# 1_dif_comp_stage.net
KiCad netlist of a schematic drawn in Altium Designer
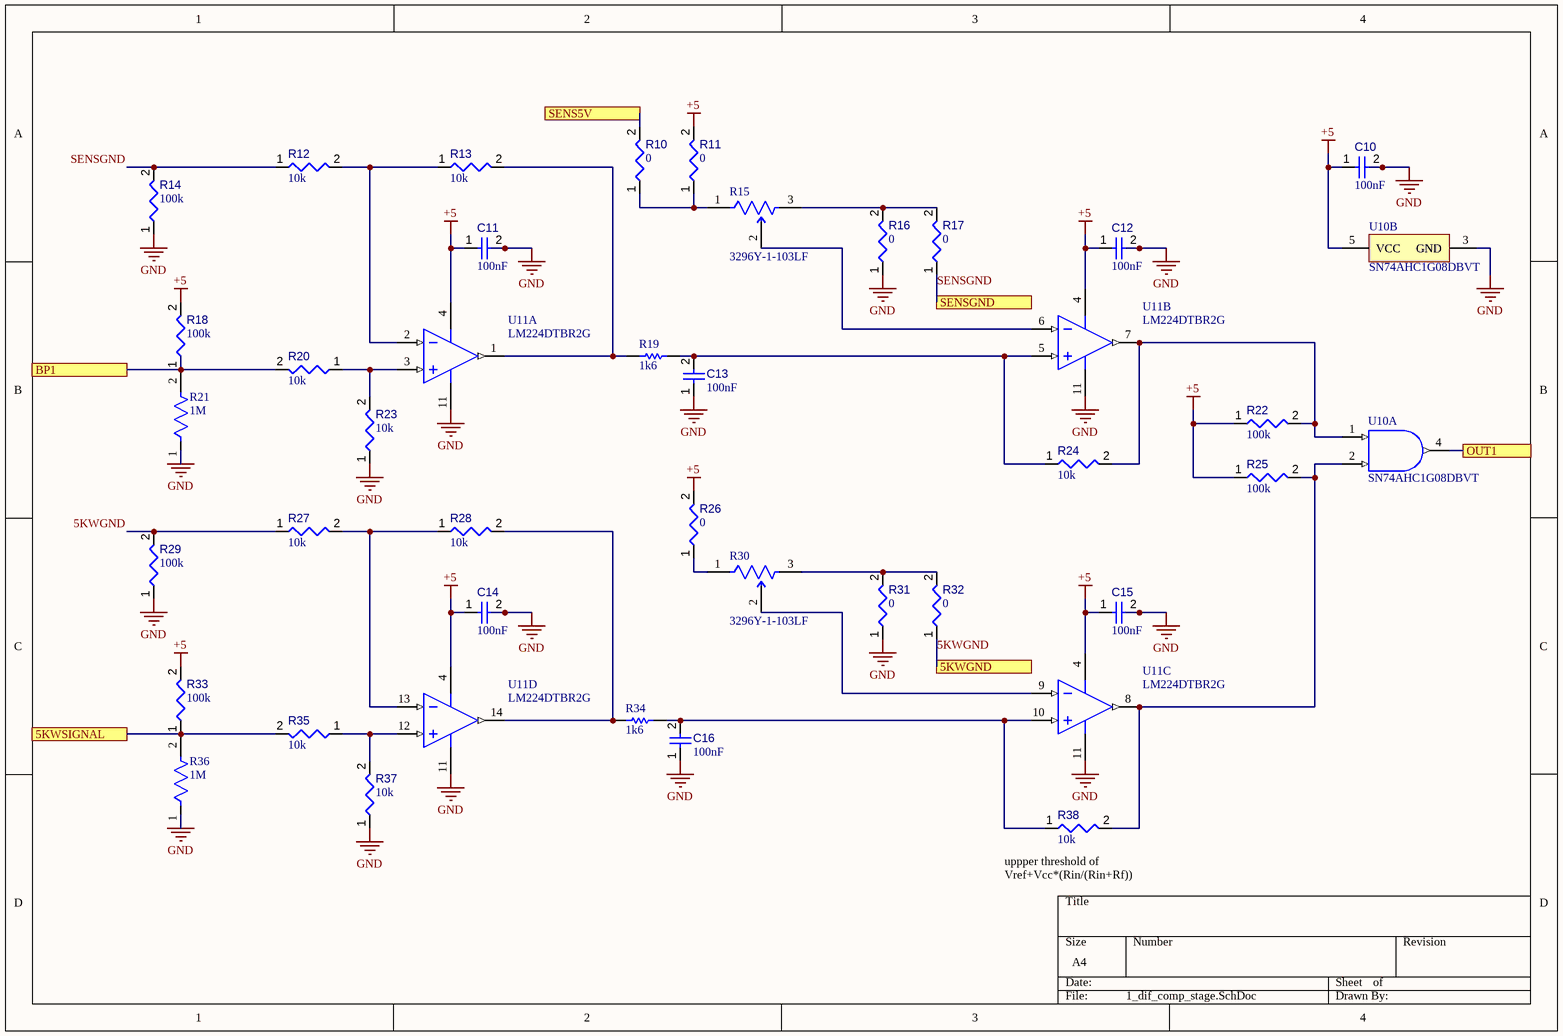
[diagram p0: 1_dif_comp_stage.SchDoc]

(export (version "E")
  (design (tool "Eeschema 10.0.6"))
  (components
    (comp (ref "C10")
      (value "100nF")
      (footprint "CAPC1608X90X40NL10T20")
      (description "Chip Capacitor, 100 nF, +/- 10%, 50 V, 0603 (1608 Metric)")
      (fields (field (name "TOLERANCE") "10%") (field (name "Comment") "Capacitor 100 nF +/-10% 50 V 0603"))
      (libsource (lib "UNSW Redback Racing") (part "CAP-NP-2"))
    )
    (comp (ref "C11")
      (value "100nF")
      (footprint "CAPC1608X90X40NL10T20")
      (description "Chip Capacitor, 100 nF, +/- 10%, 50 V, 0603 (1608 Metric)")
      (fields (field (name "TOLERANCE") "10%") (field (name "Comment") "Capacitor 100 nF +/-10% 50 V 0603"))
      (libsource (lib "UNSW Redback Racing") (part "CAP-NP-2"))
    )
    (comp (ref "C12")
      (value "100nF")
      (footprint "CAPC1608X90X40NL10T20")
      (description "Chip Capacitor, 100 nF, +/- 10%, 50 V, 0603 (1608 Metric)")
      (fields (field (name "TOLERANCE") "10%") (field (name "Comment") "Capacitor 100 nF +/-10% 50 V 0603"))
      (libsource (lib "UNSW Redback Racing") (part "CAP-NP-2"))
    )
    (comp (ref "C13")
      (value "100nF")
      (footprint "CAPC1608X90X40NL10T20")
      (description "Chip Capacitor, 100 nF, +/- 10%, 50 V, 0603 (1608 Metric)")
      (fields (field (name "TOLERANCE") "10%") (field (name "Comment") "Capacitor 100 nF +/-10% 50 V 0603"))
      (libsource (lib "UNSW Redback Racing") (part "CAP-NP-2"))
    )
    (comp (ref "C14")
      (value "100nF")
      (footprint "CAPC1608X90X40NL10T20")
      (description "Chip Capacitor, 100 nF, +/- 10%, 50 V, 0603 (1608 Metric)")
      (fields (field (name "TOLERANCE") "10%") (field (name "Comment") "Capacitor 100 nF +/-10% 50 V 0603"))
      (libsource (lib "UNSW Redback Racing") (part "CAP-NP-2"))
    )
    (comp (ref "C15")
      (value "100nF")
      (footprint "CAPC1608X90X40NL10T20")
      (description "Chip Capacitor, 100 nF, +/- 10%, 50 V, 0603 (1608 Metric)")
      (fields (field (name "TOLERANCE") "10%") (field (name "Comment") "Capacitor 100 nF +/-10% 50 V 0603"))
      (libsource (lib "UNSW Redback Racing") (part "CAP-NP-2"))
    )
    (comp (ref "C16")
      (value "100nF")
      (footprint "CAPC1608X90X40NL10T20")
      (description "Chip Capacitor, 100 nF, +/- 10%, 50 V, 0603 (1608 Metric)")
      (fields (field (name "TOLERANCE") "10%") (field (name "Comment") "Capacitor 100 nF +/-10% 50 V 0603"))
      (libsource (lib "UNSW Redback Racing") (part "CAP-NP-2"))
    )
    (comp (ref "R10")
      (value "0")
      (footprint "RESC0603(1608)_L")
      (description "Jumper 0603 (1608 Metric)")
      (fields (field (name "Comment") "0R3J"))
      (libsource (lib "UNSW Redback Racing") (part "0R3J"))
    )
    (comp (ref "R11")
      (value "0")
      (footprint "RESC0603(1608)_L")
      (description "Jumper 0603 (1608 Metric)")
      (fields (field (name "Comment") "0R3J"))
      (libsource (lib "UNSW Redback Racing") (part "0R3J"))
    )
    (comp (ref "R12")
      (value "10k")
      (footprint "RESC1608X55X25ML10T15")
      (description "Chip Resistor, 10 KOhm, +/- 1%, 01 W, -55 to 155 degC, 0603 (1608 Metric)")
      (fields (field (name "POWER") "100mW") (field (name "TOLERANCE") "1%"))
      (libsource (lib "UNSW Redback Racing") (part "RES-2"))
    )
    (comp (ref "R13")
      (value "10k")
      (footprint "RESC1608X55X25ML10T15")
      (description "Chip Resistor, 10 KOhm, +/- 1%, 01 W, -55 to 155 degC, 0603 (1608 Metric)")
      (fields (field (name "POWER") "100mW") (field (name "TOLERANCE") "1%"))
      (libsource (lib "UNSW Redback Racing") (part "RES-2"))
    )
    (comp (ref "R14")
      (value "100k")
      (footprint "RESC1608X55X25ML10T15")
      (description "Chip Resistor, 100 KOhm, +/- 1%, 0.1 W, -55 to 155 degC, 0603 (1608 Metric)")
      (fields (field (name "TOLERANCE") "1%") (field (name "POWER") "100mW"))
      (libsource (lib "UNSW Redback Racing") (part "RES-2"))
    )
    (comp (ref "R15")
      (value "3296Y-1-103LF")
      (footprint "FP-3296Y-MFG")
      (description "TRIMMER 10K OHM 0.5W PC PIN TOP")
      (fields (field (name "TOLERANCE") "10%"))
      (libsource (lib "Altium Content Vault") (part "2dcfd2547301a7d3209a5e99acfd772"))
    )
    (comp (ref "R16")
      (value "0")
      (footprint "RESC0603(1608)_L")
      (description "Jumper 0603 (1608 Metric)")
      (fields (field (name "Comment") "0R3J"))
      (libsource (lib "UNSW Redback Racing") (part "0R3J"))
    )
    (comp (ref "R17")
      (value "0")
      (footprint "RESC0603(1608)_L")
      (description "Jumper 0603 (1608 Metric)")
      (fields (field (name "Comment") "0R3J"))
      (libsource (lib "UNSW Redback Racing") (part "0R3J"))
    )
    (comp (ref "R18")
      (value "100k")
      (footprint "RESC1608X55X25ML10T15")
      (description "Chip Resistor, 100 KOhm, +/- 1%, 0.1 W, -55 to 155 degC, 0603 (1608 Metric)")
      (fields (field (name "TOLERANCE") "1%") (field (name "POWER") "100mW"))
      (libsource (lib "UNSW Redback Racing") (part "RES-2"))
    )
    (comp (ref "R19")
      (value "1k6")
      (footprint "RESC1609X50X30LL10T20")
      (fields (field (name "PART NUMBER") "CRCW06031K60FKEA") (field (name "MANUFACTURER") "Vishay Dale"))
      (libsource (lib "Altium Content Vault") (part "RES"))
    )
    (comp (ref "R20")
      (value "10k")
      (footprint "RESC1608X55X25ML10T15")
      (description "Chip Resistor, 10 KOhm, +/- 1%, 01 W, -55 to 155 degC, 0603 (1608 Metric)")
      (fields (field (name "POWER") "100mW") (field (name "TOLERANCE") "1%"))
      (libsource (lib "UNSW Redback Racing") (part "RES-2"))
    )
    (comp (ref "R21")
      (value "1M")
      (footprint "FP-RMCF0603-IPC_B")
      (description "1MΩ ±1% 0.1W 0603 Thick Film Chip Resistor AEC-Q200 compliant")
      (fields (field (name "TOLERANCE") "1%"))
      (libsource (lib "Altium Content Vault") (part "1029c3af85768c4190bb7ad29bc67b5"))
    )
    (comp (ref "R22")
      (value "100k")
      (footprint "RESC1608X55X25ML10T15")
      (description "Chip Resistor, 100 KOhm, +/- 1%, 0.1 W, -55 to 155 degC, 0603 (1608 Metric)")
      (fields (field (name "TOLERANCE") "1%") (field (name "POWER") "100mW"))
      (libsource (lib "UNSW Redback Racing") (part "RES-2"))
    )
    (comp (ref "R23")
      (value "10k")
      (footprint "RESC1608X55X25ML10T15")
      (description "Chip Resistor, 10 KOhm, +/- 1%, 01 W, -55 to 155 degC, 0603 (1608 Metric)")
      (fields (field (name "POWER") "100mW") (field (name "TOLERANCE") "1%"))
      (libsource (lib "UNSW Redback Racing") (part "RES-2"))
    )
    (comp (ref "R24")
      (value "10k")
      (footprint "RESC1608X55X25ML10T15")
      (description "Chip Resistor, 10 KOhm, +/- 1%, 01 W, -55 to 155 degC, 0603 (1608 Metric)")
      (fields (field (name "POWER") "100mW") (field (name "TOLERANCE") "1%"))
      (libsource (lib "UNSW Redback Racing") (part "RES-2"))
    )
    (comp (ref "R25")
      (value "100k")
      (footprint "RESC1608X55X25ML10T15")
      (description "Chip Resistor, 100 KOhm, +/- 1%, 0.1 W, -55 to 155 degC, 0603 (1608 Metric)")
      (fields (field (name "TOLERANCE") "1%") (field (name "POWER") "100mW"))
      (libsource (lib "UNSW Redback Racing") (part "RES-2"))
    )
    (comp (ref "R26")
      (value "0")
      (footprint "RESC0603(1608)_L")
      (description "Jumper 0603 (1608 Metric)")
      (fields (field (name "Comment") "0R3J"))
      (libsource (lib "UNSW Redback Racing") (part "0R3J"))
    )
    (comp (ref "R27")
      (value "10k")
      (footprint "RESC1608X55X25ML10T15")
      (description "Chip Resistor, 10 KOhm, +/- 1%, 01 W, -55 to 155 degC, 0603 (1608 Metric)")
      (fields (field (name "POWER") "100mW") (field (name "TOLERANCE") "1%"))
      (libsource (lib "UNSW Redback Racing") (part "RES-2"))
    )
    (comp (ref "R28")
      (value "10k")
      (footprint "RESC1608X55X25ML10T15")
      (description "Chip Resistor, 10 KOhm, +/- 1%, 01 W, -55 to 155 degC, 0603 (1608 Metric)")
      (fields (field (name "POWER") "100mW") (field (name "TOLERANCE") "1%"))
      (libsource (lib "UNSW Redback Racing") (part "RES-2"))
    )
    (comp (ref "R29")
      (value "100k")
      (footprint "RESC1608X55X25ML10T15")
      (description "Chip Resistor, 100 KOhm, +/- 1%, 0.1 W, -55 to 155 degC, 0603 (1608 Metric)")
      (fields (field (name "TOLERANCE") "1%") (field (name "POWER") "100mW"))
      (libsource (lib "UNSW Redback Racing") (part "RES-2"))
    )
    (comp (ref "R30")
      (value "3296Y-1-103LF")
      (footprint "FP-3296Y-MFG")
      (description "TRIMMER 10K OHM 0.5W PC PIN TOP")
      (fields (field (name "TOLERANCE") "10%"))
      (libsource (lib "Altium Content Vault") (part "2dcfd2547301a7d3209a5e99acfd772"))
    )
    (comp (ref "R31")
      (value "0")
      (footprint "RESC0603(1608)_L")
      (description "Jumper 0603 (1608 Metric)")
      (fields (field (name "Comment") "0R3J"))
      (libsource (lib "UNSW Redback Racing") (part "0R3J"))
    )
    (comp (ref "R32")
      (value "0")
      (footprint "RESC0603(1608)_L")
      (description "Jumper 0603 (1608 Metric)")
      (fields (field (name "Comment") "0R3J"))
      (libsource (lib "UNSW Redback Racing") (part "0R3J"))
    )
    (comp (ref "R33")
      (value "100k")
      (footprint "RESC1608X55X25ML10T15")
      (description "Chip Resistor, 100 KOhm, +/- 1%, 0.1 W, -55 to 155 degC, 0603 (1608 Metric)")
      (fields (field (name "TOLERANCE") "1%") (field (name "POWER") "100mW"))
      (libsource (lib "UNSW Redback Racing") (part "RES-2"))
    )
    (comp (ref "R34")
      (value "1k6")
      (footprint "RESC1609X50X30LL10T20")
      (fields (field (name "PART NUMBER") "CRCW06031K60FKEA") (field (name "MANUFACTURER") "Vishay Dale"))
      (libsource (lib "Altium Content Vault") (part "RES"))
    )
    (comp (ref "R35")
      (value "10k")
      (footprint "RESC1608X55X25ML10T15")
      (description "Chip Resistor, 10 KOhm, +/- 1%, 01 W, -55 to 155 degC, 0603 (1608 Metric)")
      (fields (field (name "POWER") "100mW") (field (name "TOLERANCE") "1%"))
      (libsource (lib "UNSW Redback Racing") (part "RES-2"))
    )
    (comp (ref "R36")
      (value "1M")
      (footprint "FP-RMCF0603-IPC_B")
      (description "1MΩ ±1% 0.1W 0603 Thick Film Chip Resistor AEC-Q200 compliant")
      (fields (field (name "TOLERANCE") "1%"))
      (libsource (lib "Altium Content Vault") (part "1029c3af85768c4190bb7ad29bc67b5"))
    )
    (comp (ref "R37")
      (value "10k")
      (footprint "RESC1608X55X25ML10T15")
      (description "Chip Resistor, 10 KOhm, +/- 1%, 01 W, -55 to 155 degC, 0603 (1608 Metric)")
      (fields (field (name "POWER") "100mW") (field (name "TOLERANCE") "1%"))
      (libsource (lib "UNSW Redback Racing") (part "RES-2"))
    )
    (comp (ref "R38")
      (value "10k")
      (footprint "RESC1608X55X25ML10T15")
      (description "Chip Resistor, 10 KOhm, +/- 1%, 01 W, -55 to 155 degC, 0603 (1608 Metric)")
      (fields (field (name "POWER") "100mW") (field (name "TOLERANCE") "1%"))
      (libsource (lib "UNSW Redback Racing") (part "RES-2"))
    )
    (comp (ref "U10")
      (value "SN74AHC1G08DBVT")
      (footprint "DBV0005A_L")
      (description "Single 2-Input Positive-AND Gate, DBV0005A, SMALL T&R")
      (fields
        (field (name "GENERIC PART NUMBER") "SN74AHC1G08")
        (field (name "MANUFACTURER") "Texas Instruments")
      )
      (libsource (lib "Altium Content Vault") (part "TI-SN74XXX1X08-5"))
    )
    (comp (ref "U11")
      (value "LM224DTBR2G")
      (footprint "ONSC-TSSOP-14-948G-01_V")
      (fields (field (name "MANUFACTURER") "On Semiconductor"))
      (libsource (lib "Altium Content Vault") (part "ONSC-LM224_324_2902_NCV2902-14"))
    )
  )
  (nets
    (net (code "1") (name "+5") (class "Default")
      (node (ref "C10") (pin "1") (pinfunction "1_1") (pintype "passive"))
      (node (ref "C11") (pin "1") (pinfunction "1_1") (pintype "passive"))
      (node (ref "C12") (pin "1") (pinfunction "1_1") (pintype "passive"))
      (node (ref "C14") (pin "1") (pinfunction "1_1") (pintype "passive"))
      (node (ref "C15") (pin "1") (pinfunction "1_1") (pintype "passive"))
      (node (ref "R11") (pin "2") (pinfunction "2_2") (pintype "passive"))
      (node (ref "R18") (pin "2") (pinfunction "2_2") (pintype "passive"))
      (node (ref "R22") (pin "1") (pinfunction "1_1") (pintype "passive"))
      (node (ref "R25") (pin "1") (pinfunction "1_1") (pintype "passive"))
      (node (ref "R26") (pin "2") (pinfunction "2_2") (pintype "passive"))
      (node (ref "R33") (pin "2") (pinfunction "2_2") (pintype "passive"))
      (node (ref "U10") (pin "5") (pinfunction "VCC_5") (pintype "power_in"))
      (node (ref "U11") (pin "4") (pinfunction "VCC_4") (pintype "power_in"))
    )
    (net (code "2") (name "/5KWGND") (class "Default")
      (node (ref "R27") (pin "1") (pinfunction "1_1") (pintype "passive"))
      (node (ref "R29") (pin "2") (pinfunction "2_2") (pintype "passive"))
      (node (ref "R32") (pin "1") (pinfunction "1_1") (pintype "passive"))
    )
    (net (code "3") (name "/5KWSIGNAL") (class "Default")
      (node (ref "R33") (pin "1") (pinfunction "1_1") (pintype "passive"))
      (node (ref "R35") (pin "2") (pinfunction "2_2") (pintype "passive"))
      (node (ref "R36") (pin "2") (pinfunction "2_2") (pintype "passive"))
    )
    (net (code "4") (name "/BP1") (class "Default")
      (node (ref "R18") (pin "1") (pinfunction "1_1") (pintype "passive"))
      (node (ref "R20") (pin "2") (pinfunction "2_2") (pintype "passive"))
      (node (ref "R21") (pin "2") (pinfunction "2_2") (pintype "passive"))
    )
    (net (code "5") (name "/OUT1") (class "Default")
      (node (ref "U10") (pin "4") (pinfunction "Y_4") (pintype "output"))
    )
    (net (code "6") (name "/SENS5V") (class "Default")
      (node (ref "R10") (pin "2") (pinfunction "2_2") (pintype "passive"))
    )
    (net (code "7") (name "/SENSGND") (class "Default")
      (node (ref "R12") (pin "1") (pinfunction "1_1") (pintype "passive"))
      (node (ref "R14") (pin "2") (pinfunction "2_2") (pintype "passive"))
      (node (ref "R17") (pin "1") (pinfunction "1_1") (pintype "passive"))
    )
    (net (code "8") (name "GND") (class "Default")
      (node (ref "C10") (pin "2") (pinfunction "2_2") (pintype "passive"))
      (node (ref "C11") (pin "2") (pinfunction "2_2") (pintype "passive"))
      (node (ref "C12") (pin "2") (pinfunction "2_2") (pintype "passive"))
      (node (ref "C13") (pin "1") (pinfunction "1_1") (pintype "passive"))
      (node (ref "C14") (pin "2") (pinfunction "2_2") (pintype "passive"))
      (node (ref "C15") (pin "2") (pinfunction "2_2") (pintype "passive"))
      (node (ref "C16") (pin "1") (pinfunction "1_1") (pintype "passive"))
      (node (ref "R14") (pin "1") (pinfunction "1_1") (pintype "passive"))
      (node (ref "R16") (pin "1") (pinfunction "1_1") (pintype "passive"))
      (node (ref "R21") (pin "1") (pinfunction "1_1") (pintype "passive"))
      (node (ref "R23") (pin "1") (pinfunction "1_1") (pintype "passive"))
      (node (ref "R29") (pin "1") (pinfunction "1_1") (pintype "passive"))
      (node (ref "R31") (pin "1") (pinfunction "1_1") (pintype "passive"))
      (node (ref "R36") (pin "1") (pinfunction "1_1") (pintype "passive"))
      (node (ref "R37") (pin "1") (pinfunction "1_1") (pintype "passive"))
      (node (ref "U10") (pin "3") (pinfunction "GND_3") (pintype "power_in"))
      (node (ref "U11") (pin "11") (pinfunction "VEE/GND_11") (pintype "power_in"))
    )
    (net (code "9") (name "Net-(R15-CCW)") (class "Default")
      (node (ref "R10") (pin "1") (pinfunction "1_1") (pintype "passive"))
      (node (ref "R11") (pin "1") (pinfunction "1_1") (pintype "passive"))
      (node (ref "R15") (pin "1") (pinfunction "CCW_1") (pintype "passive"))
    )
    (net (code "10") (name "Net-(R15-CW)") (class "Default")
      (node (ref "R15") (pin "3") (pinfunction "CW_3") (pintype "passive"))
      (node (ref "R16") (pin "2") (pinfunction "2_2") (pintype "passive"))
      (node (ref "R17") (pin "2") (pinfunction "2_2") (pintype "passive"))
    )
    (net (code "11") (name "Net-(R15-WIPER)") (class "Default")
      (node (ref "R15") (pin "2") (pinfunction "WIPER_2") (pintype "passive"))
      (node (ref "U11") (pin "6") (pinfunction "IN2-_6") (pintype "input"))
    )
    (net (code "12") (name "Net-(R30-CCW)") (class "Default")
      (node (ref "R26") (pin "1") (pinfunction "1_1") (pintype "passive"))
      (node (ref "R30") (pin "1") (pinfunction "CCW_1") (pintype "passive"))
    )
    (net (code "13") (name "Net-(R30-CW)") (class "Default")
      (node (ref "R30") (pin "3") (pinfunction "CW_3") (pintype "passive"))
      (node (ref "R31") (pin "2") (pinfunction "2_2") (pintype "passive"))
      (node (ref "R32") (pin "2") (pinfunction "2_2") (pintype "passive"))
    )
    (net (code "14") (name "Net-(R30-WIPER)") (class "Default")
      (node (ref "R30") (pin "2") (pinfunction "WIPER_2") (pintype "passive"))
      (node (ref "U11") (pin "9") (pinfunction "IN3-_9") (pintype "input"))
    )
    (net (code "15") (name "Net-(U10A-A)") (class "Default")
      (node (ref "R22") (pin "2") (pinfunction "2_2") (pintype "passive"))
      (node (ref "R24") (pin "2") (pinfunction "2_2") (pintype "passive"))
      (node (ref "U10") (pin "1") (pinfunction "A_1") (pintype "input"))
      (node (ref "U11") (pin "7") (pinfunction "OUT2_7") (pintype "output"))
    )
    (net (code "16") (name "Net-(U10A-B)") (class "Default")
      (node (ref "R25") (pin "2") (pinfunction "2_2") (pintype "passive"))
      (node (ref "R38") (pin "2") (pinfunction "2_2") (pintype "passive"))
      (node (ref "U10") (pin "2") (pinfunction "B_2") (pintype "input"))
      (node (ref "U11") (pin "8") (pinfunction "OUT3_8") (pintype "output"))
    )
    (net (code "17") (name "Net-(U11A-IN1+)") (class "Default")
      (node (ref "R20") (pin "1") (pinfunction "1_1") (pintype "passive"))
      (node (ref "R23") (pin "2") (pinfunction "2_2") (pintype "passive"))
      (node (ref "U11") (pin "3") (pinfunction "IN1+_3") (pintype "input"))
    )
    (net (code "18") (name "Net-(U11A-IN1-)") (class "Default")
      (node (ref "R12") (pin "2") (pinfunction "2_2") (pintype "passive"))
      (node (ref "R13") (pin "1") (pinfunction "1_1") (pintype "passive"))
      (node (ref "U11") (pin "2") (pinfunction "IN1-_2") (pintype "input"))
    )
    (net (code "19") (name "Net-(U11A-OUT1)") (class "Default")
      (node (ref "R13") (pin "2") (pinfunction "2_2") (pintype "passive"))
      (node (ref "R19") (pin "1") (pinfunction "1_1") (pintype "passive"))
      (node (ref "U11") (pin "1") (pinfunction "OUT1_1") (pintype "output"))
    )
    (net (code "20") (name "Net-(U11B-IN2+)") (class "Default")
      (node (ref "C13") (pin "2") (pinfunction "2_2") (pintype "passive"))
      (node (ref "R19") (pin "2") (pinfunction "2_2") (pintype "passive"))
      (node (ref "R24") (pin "1") (pinfunction "1_1") (pintype "passive"))
      (node (ref "U11") (pin "5") (pinfunction "IN2+_5") (pintype "input"))
    )
    (net (code "21") (name "Net-(U11C-IN3+)") (class "Default")
      (node (ref "C16") (pin "2") (pinfunction "2_2") (pintype "passive"))
      (node (ref "R34") (pin "2") (pinfunction "2_2") (pintype "passive"))
      (node (ref "R38") (pin "1") (pinfunction "1_1") (pintype "passive"))
      (node (ref "U11") (pin "10") (pinfunction "IN3+_10") (pintype "input"))
    )
    (net (code "22") (name "Net-(U11D-IN4+)") (class "Default")
      (node (ref "R35") (pin "1") (pinfunction "1_1") (pintype "passive"))
      (node (ref "R37") (pin "2") (pinfunction "2_2") (pintype "passive"))
      (node (ref "U11") (pin "12") (pinfunction "IN4+_12") (pintype "input"))
    )
    (net (code "23") (name "Net-(U11D-IN4-)") (class "Default")
      (node (ref "R27") (pin "2") (pinfunction "2_2") (pintype "passive"))
      (node (ref "R28") (pin "1") (pinfunction "1_1") (pintype "passive"))
      (node (ref "U11") (pin "13") (pinfunction "IN4-_13") (pintype "input"))
    )
    (net (code "24") (name "Net-(U11D-OUT4)") (class "Default")
      (node (ref "R28") (pin "2") (pinfunction "2_2") (pintype "passive"))
      (node (ref "R34") (pin "1") (pinfunction "1_1") (pintype "passive"))
      (node (ref "U11") (pin "14") (pinfunction "OUT4_14") (pintype "output"))
    )
  )
)
